# temperature.net
KiCad netlist of a schematic drawn in Altium Designer
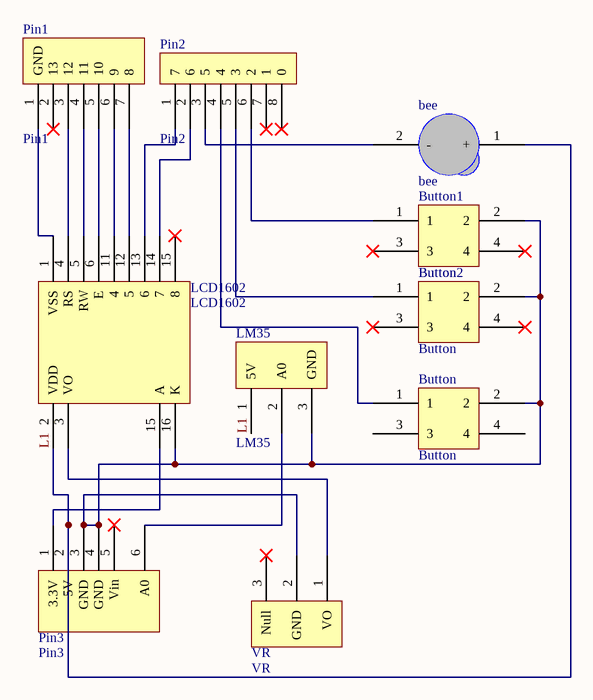
[diagram p0: temperature.SchDoc]

(export (version "E")
  (design (tool "Eeschema 10.0.6"))
  (components
    (comp (ref "bee") (value "bee") (footprint "bee") (libsource (lib "TemperatureLib") (part "bee")))
    (comp (ref "Button")
      (value "Button")
      (footprint "button")
      (libsource (lib "TemperatureLib") (part "Button"))
    )
    (comp (ref "Button1")
      (value "Button")
      (footprint "button")
      (libsource (lib "TemperatureLib") (part "Button"))
    )
    (comp (ref "Button2")
      (value "Button")
      (footprint "button")
      (libsource (lib "TemperatureLib") (part "Button"))
    )
    (comp (ref "LCD1602")
      (value "LCD1602")
      (footprint "LCD1602")
      (libsource (lib "TemperatureLib") (part "LCD1602"))
    )
    (comp (ref "LM35") (value "LM35") (footprint "LM35") (libsource (lib "TemperatureLib") (part "LM35")))
    (comp (ref "Pin1") (value "Pin1") (footprint "Pin1") (libsource (lib "TemperatureLib") (part "Pin1")))
    (comp (ref "Pin2") (value "Pin2") (footprint "Pin2") (libsource (lib "TemperatureLib") (part "Pin2")))
    (comp (ref "Pin3") (value "Pin3") (footprint "Pin3") (libsource (lib "TemperatureLib") (part "Pin3")))
    (comp (ref "VR") (value "VR") (footprint "VR") (libsource (lib "TemperatureLib") (part "VR")))
  )
  (nets
    (net (code "1") (name "/L1") (class "Default")
      (node (ref "LCD1602") (pin "2") (pinfunction "VDD_2") (pintype "passive"))
      (node (ref "LM35") (pin "1") (pinfunction "5V_1") (pintype "passive"))
      (node (ref "Pin3") (pin "2") (pinfunction "5V_2") (pintype "passive"))
      (node (ref "bee") (pin "1") (pinfunction "+_1") (pintype "passive"))
    )
    (net (code "2") (name "Net-(Button-Pad1)") (class "Default")
      (node (ref "Button") (pin "1") (pinfunction "1_1") (pintype "passive"))
      (node (ref "Pin2") (pin "4") (pinfunction "4_4") (pintype "passive"))
    )
    (net (code "3") (name "Net-(LCD1602-4)") (class "Default")
      (node (ref "LCD1602") (pin "11") (pinfunction "4_11") (pintype "passive"))
      (node (ref "Pin1") (pin "6") (pinfunction "9_6") (pintype "passive"))
    )
    (net (code "4") (name "Net-(LCD1602-5)") (class "Default")
      (node (ref "LCD1602") (pin "12") (pinfunction "5_12") (pintype "passive"))
      (node (ref "Pin1") (pin "7") (pinfunction "8_7") (pintype "passive"))
    )
    (net (code "5") (name "Net-(LCD1602-6)") (class "Default")
      (node (ref "LCD1602") (pin "13") (pinfunction "6_13") (pintype "passive"))
      (node (ref "Pin2") (pin "1") (pinfunction "7_1") (pintype "passive"))
    )
    (net (code "6") (name "Net-(LCD1602-7)") (class "Default")
      (node (ref "LCD1602") (pin "14") (pinfunction "7_14") (pintype "passive"))
      (node (ref "Pin2") (pin "2") (pinfunction "6_2") (pintype "passive"))
    )
    (net (code "7") (name "Net-(LCD1602-A)") (class "Default")
      (node (ref "LCD1602") (pin "15") (pinfunction "A_15") (pintype "passive"))
      (node (ref "Pin3") (pin "1") (pinfunction "3.3V_1") (pintype "passive"))
    )
    (net (code "8") (name "Net-(LCD1602-E)") (class "Default")
      (node (ref "LCD1602") (pin "6") (pinfunction "E_6") (pintype "passive"))
      (node (ref "Pin1") (pin "5") (pinfunction "10_5") (pintype "passive"))
    )
    (net (code "9") (name "Net-(LCD1602-K)") (class "Default")
      (node (ref "Button") (pin "2") (pinfunction "2_2") (pintype "passive"))
      (node (ref "Button1") (pin "2") (pinfunction "2_2") (pintype "passive"))
      (node (ref "Button2") (pin "2") (pinfunction "2_2") (pintype "passive"))
      (node (ref "LCD1602") (pin "16") (pinfunction "K_16") (pintype "passive"))
      (node (ref "LM35") (pin "3") (pinfunction "GND_3") (pintype "passive"))
      (node (ref "Pin3") (pin "3") (pinfunction "GND_3") (pintype "passive"))
      (node (ref "Pin3") (pin "4") (pinfunction "GND_4") (pintype "passive"))
      (node (ref "VR") (pin "2") (pinfunction "GND_2") (pintype "passive"))
    )
    (net (code "10") (name "Net-(LCD1602-RS)") (class "Default")
      (node (ref "LCD1602") (pin "4") (pinfunction "RS_4") (pintype "passive"))
      (node (ref "Pin1") (pin "3") (pinfunction "12_3") (pintype "passive"))
    )
    (net (code "11") (name "Net-(LCD1602-RW)") (class "Default")
      (node (ref "LCD1602") (pin "5") (pinfunction "RW_5") (pintype "passive"))
      (node (ref "Pin1") (pin "4") (pinfunction "11_4") (pintype "passive"))
    )
    (net (code "12") (name "Net-(LCD1602-VO)") (class "Default")
      (node (ref "LCD1602") (pin "3") (pinfunction "VO_3") (pintype "passive"))
      (node (ref "VR") (pin "1") (pinfunction "VO_1") (pintype "passive"))
    )
    (net (code "13") (name "Net-(LCD1602-VSS)") (class "Default")
      (node (ref "LCD1602") (pin "1") (pinfunction "VSS_1") (pintype "passive"))
      (node (ref "Pin1") (pin "1") (pinfunction "GND_1") (pintype "passive"))
    )
    (net (code "14") (name "Net-(LM35-A0)") (class "Default")
      (node (ref "LM35") (pin "2") (pinfunction "A0_2") (pintype "passive"))
      (node (ref "Pin3") (pin "6") (pinfunction "A0_6") (pintype "passive"))
    )
    (net (code "15") (name "Net-(Pin2-2)") (class "Default")
      (node (ref "Button1") (pin "1") (pinfunction "1_1") (pintype "passive"))
      (node (ref "Pin2") (pin "6") (pinfunction "2_6") (pintype "passive"))
    )
    (net (code "16") (name "Net-(Pin2-3)") (class "Default")
      (node (ref "Button2") (pin "1") (pinfunction "1_1") (pintype "passive"))
      (node (ref "Pin2") (pin "5") (pinfunction "3_5") (pintype "passive"))
    )
    (net (code "17") (name "Net-(Pin2-5)") (class "Default")
      (node (ref "Pin2") (pin "3") (pinfunction "5_3") (pintype "passive"))
      (node (ref "bee") (pin "2") (pinfunction "-_2") (pintype "passive"))
    )
    (net (code "18") (name "unconnected-(Button-Pad3)") (class "Default")
      (node (ref "Button") (pin "3") (pinfunction "3_3") (pintype "passive"))
    )
    (net (code "19") (name "unconnected-(Button-Pad4)") (class "Default")
      (node (ref "Button") (pin "4") (pinfunction "4_4") (pintype "passive"))
    )
    (net (code "20") (name "unconnected-(Button1-Pad3)") (class "Default")
      (node (ref "Button1") (pin "3") (pinfunction "3_3") (pintype "passive+no_connect"))
    )
    (net (code "21") (name "unconnected-(Button1-Pad4)") (class "Default")
      (node (ref "Button1") (pin "4") (pinfunction "4_4") (pintype "passive+no_connect"))
    )
    (net (code "22") (name "unconnected-(Button2-Pad3)") (class "Default")
      (node (ref "Button2") (pin "3") (pinfunction "3_3") (pintype "passive+no_connect"))
    )
    (net (code "23") (name "unconnected-(Button2-Pad4)") (class "Default")
      (node (ref "Button2") (pin "4") (pinfunction "4_4") (pintype "passive+no_connect"))
    )
    (net (code "24") (name "unconnected-(LCD1602-8-Pad15)") (class "Default")
      (node (ref "LCD1602") (pin "15") (pinfunction "8_15") (pintype "passive+no_connect"))
    )
    (net (code "25") (name "unconnected-(Pin1-13-Pad2)") (class "Default")
      (node (ref "Pin1") (pin "2") (pinfunction "13_2") (pintype "passive+no_connect"))
    )
    (net (code "26") (name "unconnected-(Pin2-0-Pad8)") (class "Default")
      (node (ref "Pin2") (pin "8") (pinfunction "0_8") (pintype "passive+no_connect"))
    )
    (net (code "27") (name "unconnected-(Pin2-1-Pad7)") (class "Default")
      (node (ref "Pin2") (pin "7") (pinfunction "1_7") (pintype "passive+no_connect"))
    )
    (net (code "28") (name "unconnected-(Pin3-Vin-Pad5)") (class "Default")
      (node (ref "Pin3") (pin "5") (pinfunction "Vin_5") (pintype "passive+no_connect"))
    )
    (net (code "29") (name "unconnected-(VR-Null-Pad3)") (class "Default")
      (node (ref "VR") (pin "3") (pinfunction "Null_3") (pintype "passive+no_connect"))
    )
  )
)
